# CCM_0023_revB.net
KiCad netlist of a schematic drawn in EAGLE
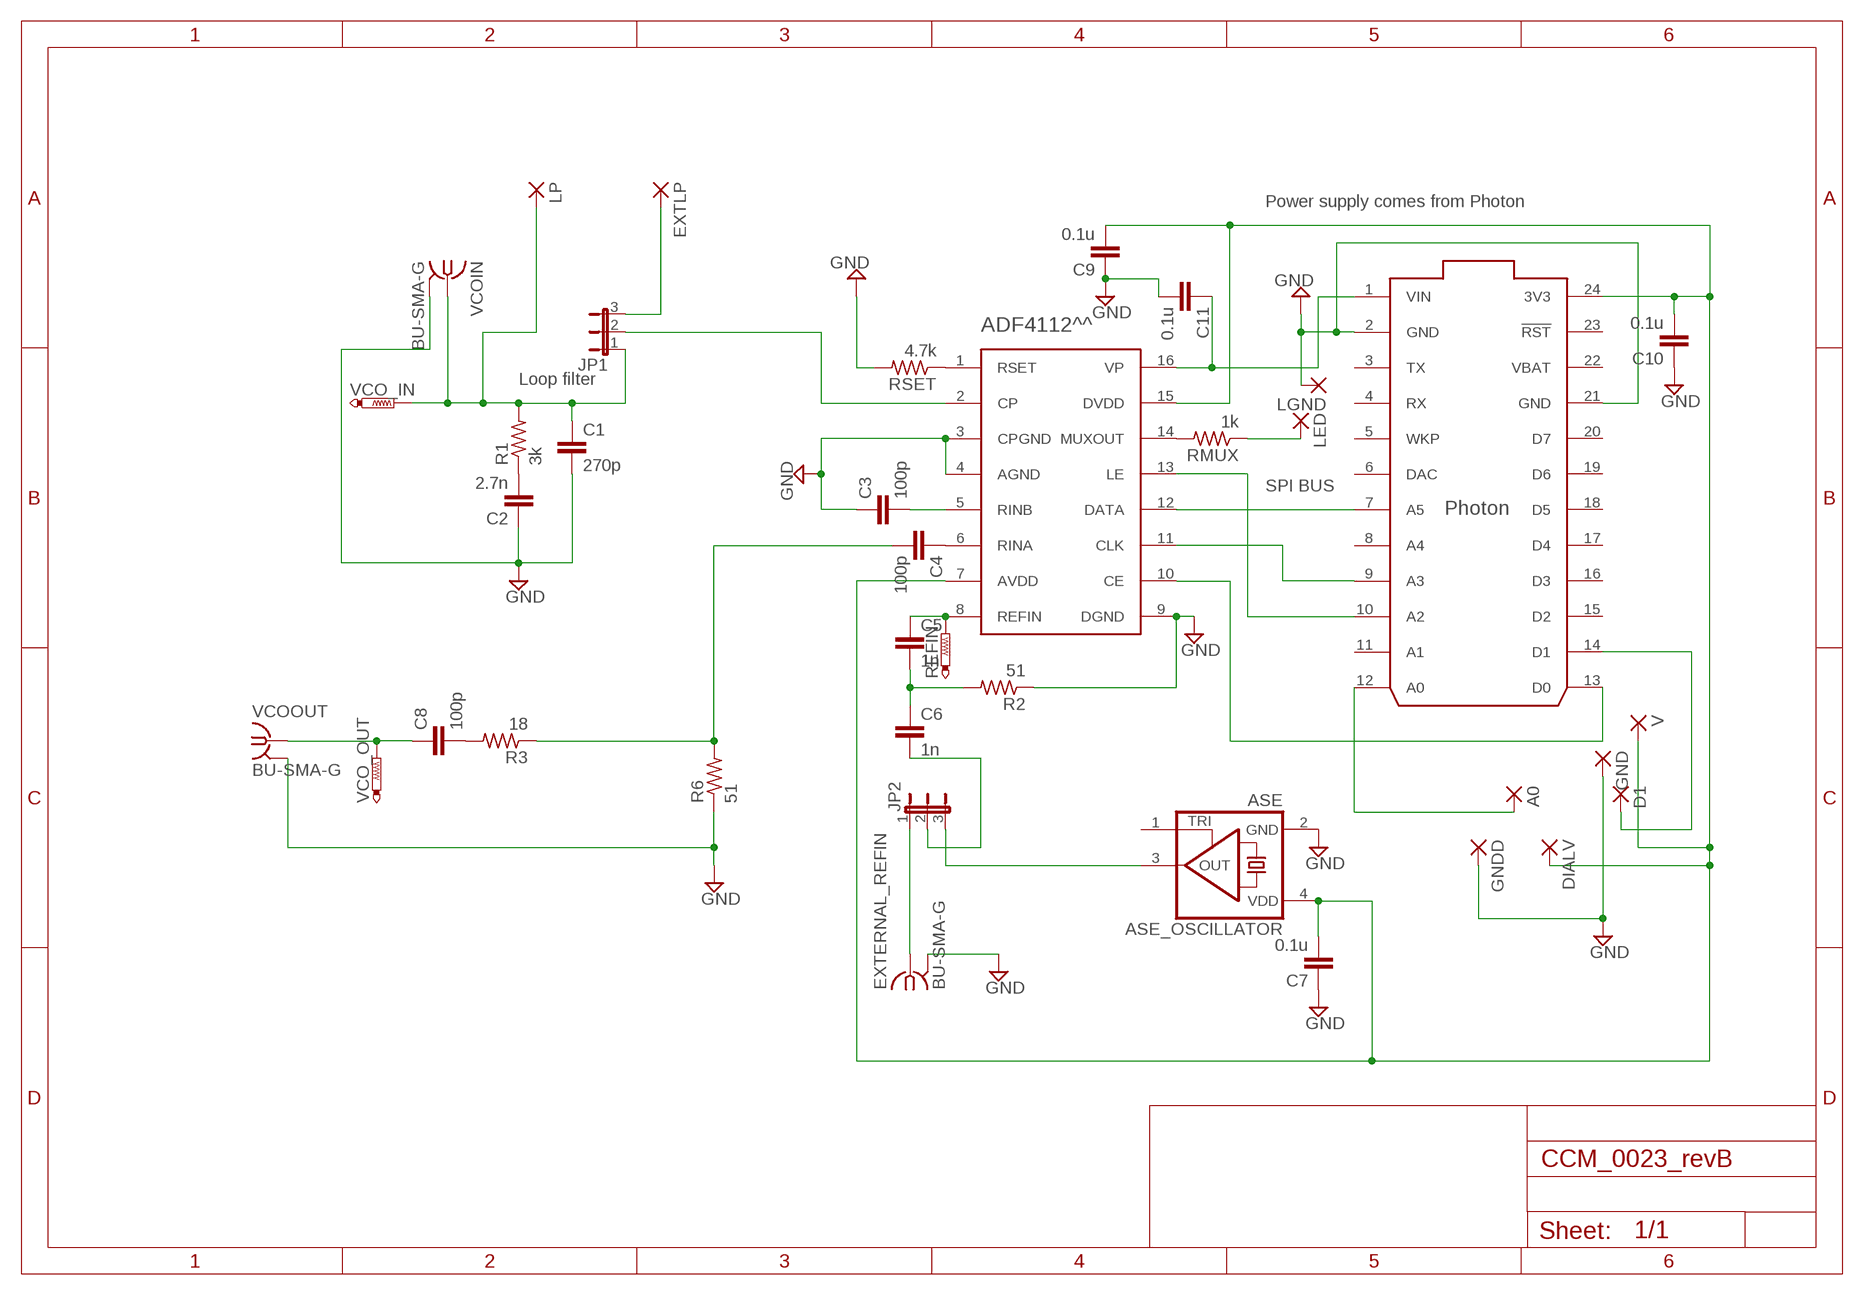
[diagram p0: schematic, sheet 1]

(export (version "E")
  (design (tool "Eeschema 10.0.6"))
  (components
    (comp (ref "A0")
      (value "1,6/0,8")
      (footprint "eagle-import:1,6_0,8")
      (libsource (lib "eagle-import") (part "1,6/0,8"))
    )
    (comp (ref "ADF4112^^")
      (value "ADF4112")
      (footprint "eagle-import:ADF4112")
      (libsource (lib "eagle-import") (part "ADF4112"))
    )
    (comp (ref "ASE_OSCILLATOR")
      (value "ASE")
      (footprint "eagle-import:ASE")
      (libsource (lib "eagle-import") (part "ASE"))
    )
    (comp (ref "C1")
      (value "270p")
      (footprint "eagle-import:C0603")
      (libsource (lib "eagle-import") (part "CC0603"))
    )
    (comp (ref "C2")
      (value "2.7n")
      (footprint "eagle-import:C0603")
      (libsource (lib "eagle-import") (part "CC0603"))
    )
    (comp (ref "C3")
      (value "100p")
      (footprint "eagle-import:C0603")
      (libsource (lib "eagle-import") (part "CC0603"))
    )
    (comp (ref "C4")
      (value "100p")
      (footprint "eagle-import:C0603")
      (libsource (lib "eagle-import") (part "CC0603"))
    )
    (comp (ref "C5")
      (value "1n")
      (footprint "eagle-import:C0603")
      (libsource (lib "eagle-import") (part "CC0603"))
    )
    (comp (ref "C6")
      (value "1n")
      (footprint "eagle-import:C0603")
      (libsource (lib "eagle-import") (part "CC0603"))
    )
    (comp (ref "C7")
      (value "0.1u")
      (footprint "eagle-import:C0603")
      (libsource (lib "eagle-import") (part "CC0603"))
    )
    (comp (ref "C8")
      (value "100p")
      (footprint "eagle-import:C0603")
      (libsource (lib "eagle-import") (part "CC0603"))
    )
    (comp (ref "C9")
      (value "0.1u")
      (footprint "eagle-import:C0603")
      (libsource (lib "eagle-import") (part "CC0603"))
    )
    (comp (ref "C10")
      (value "0.1u")
      (footprint "eagle-import:C0603")
      (libsource (lib "eagle-import") (part "CC0603"))
    )
    (comp (ref "C11")
      (value "0.1u")
      (footprint "eagle-import:C0603")
      (libsource (lib "eagle-import") (part "CC0603"))
    )
    (comp (ref "D1")
      (value "1,6/0,8")
      (footprint "eagle-import:1,6_0,8")
      (libsource (lib "eagle-import") (part "1,6/0,8"))
    )
    (comp (ref "DIALV")
      (value "1,6/0,8")
      (footprint "eagle-import:1,6_0,8")
      (libsource (lib "eagle-import") (part "1,6/0,8"))
    )
    (comp (ref "EXTERNAL_REFIN")
      (value "BU-SMA-G")
      (footprint "eagle-import:BU-SMA-G")
      (libsource (lib "eagle-import") (part "BU-SMA-G"))
    )
    (comp (ref "EXTLP")
      (value "1,6/0,8")
      (footprint "eagle-import:1,6_0,8")
      (libsource (lib "eagle-import") (part "1,6/0,8"))
    )
    (comp (ref "GND")
      (value "1,6/0,8")
      (footprint "eagle-import:1,6_0,8")
      (libsource (lib "eagle-import") (part "1,6/0,8"))
    )
    (comp (ref "GNDD")
      (value "1,6/0,8")
      (footprint "eagle-import:1,6_0,8")
      (libsource (lib "eagle-import") (part "1,6/0,8"))
    )
    (comp (ref "JP1")
      (value "JP2E")
      (footprint "eagle-import:JP2")
      (libsource (lib "eagle-import") (part "JP2E"))
    )
    (comp (ref "JP2")
      (value "JP2E")
      (footprint "eagle-import:JP2")
      (libsource (lib "eagle-import") (part "JP2E"))
    )
    (comp (ref "LED")
      (value "1,6/0,8")
      (footprint "eagle-import:1,6_0,8")
      (libsource (lib "eagle-import") (part "1,6/0,8"))
    )
    (comp (ref "LGND")
      (value "1,6/0,8")
      (footprint "eagle-import:1,6_0,8")
      (libsource (lib "eagle-import") (part "1,6/0,8"))
    )
    (comp (ref "LP")
      (value "1,6/0,8")
      (footprint "eagle-import:1,6_0,8")
      (libsource (lib "eagle-import") (part "1,6/0,8"))
    )
    (comp (ref "PHOTON")
      (value "PHOTON_WITH_HEADERS")
      (footprint "eagle-import:PHOTON")
      (libsource (lib "eagle-import") (part "PHOTON_WITH_HEADERS"))
    )
    (comp (ref "R1")
      (value "3k")
      (footprint "eagle-import:R0603")
      (libsource (lib "eagle-import") (part "R-US_R0603"))
    )
    (comp (ref "R2")
      (value "51")
      (footprint "eagle-import:R0603")
      (libsource (lib "eagle-import") (part "R-US_R0603"))
    )
    (comp (ref "R3")
      (value "18")
      (footprint "eagle-import:R0603")
      (libsource (lib "eagle-import") (part "R-US_R0603"))
    )
    (comp (ref "R6")
      (value "51")
      (footprint "eagle-import:R0603")
      (libsource (lib "eagle-import") (part "R-US_R0603"))
    )
    (comp (ref "REFIN")
      (value "PTR1B2,54")
      (footprint "eagle-import:B2,54")
      (libsource (lib "eagle-import") (part "PTR1B2,54"))
    )
    (comp (ref "RMUX")
      (value "1k")
      (footprint "eagle-import:R0603")
      (libsource (lib "eagle-import") (part "R-US_R0603"))
    )
    (comp (ref "RSET")
      (value "4.7k")
      (footprint "eagle-import:R0603")
      (libsource (lib "eagle-import") (part "R-US_R0603"))
    )
    (comp (ref "V")
      (value "1,6/0,8")
      (footprint "eagle-import:1,6_0,8")
      (libsource (lib "eagle-import") (part "1,6/0,8"))
    )
    (comp (ref "VCOIN")
      (value "BU-SMA-G")
      (footprint "eagle-import:BU-SMA-G")
      (libsource (lib "eagle-import") (part "BU-SMA-G"))
    )
    (comp (ref "VCOOUT")
      (value "BU-SMA-G")
      (footprint "eagle-import:BU-SMA-G")
      (libsource (lib "eagle-import") (part "BU-SMA-G"))
    )
    (comp (ref "VCO_IN")
      (value "PTR1B2,54")
      (footprint "eagle-import:B2,54")
      (libsource (lib "eagle-import") (part "PTR1B2,54"))
    )
    (comp (ref "VCO_OUT")
      (value "PTR1B2,54")
      (footprint "eagle-import:B2,54")
      (libsource (lib "eagle-import") (part "PTR1B2,54"))
    )
  )
  (nets
    (net (code "1") (name "/VBAT") (class "Default")
      (node (ref "PHOTON") (pin "22") (pinfunction "VBAT_22") (pintype "power_in"))
    )
    (net (code "2") (name "GND") (class "Default")
      (node (ref "ADF4112^^") (pin "3") (pinfunction "CPGND_3") (pintype "bidirectional"))
      (node (ref "ADF4112^^") (pin "4") (pinfunction "AGND_4") (pintype "bidirectional"))
      (node (ref "ADF4112^^") (pin "9") (pinfunction "DGND_9") (pintype "bidirectional"))
      (node (ref "ASE_OSCILLATOR") (pin "2") (pinfunction "GND_2") (pintype "power_in"))
      (node (ref "C1") (pin "2") (pinfunction "2_2") (pintype "passive"))
      (node (ref "C10") (pin "1") (pinfunction "1_1") (pintype "passive"))
      (node (ref "C11") (pin "2") (pinfunction "2_2") (pintype "passive"))
      (node (ref "C2") (pin "1") (pinfunction "1_1") (pintype "passive"))
      (node (ref "C3") (pin "1") (pinfunction "1_1") (pintype "passive"))
      (node (ref "C7") (pin "1") (pinfunction "1_1") (pintype "passive"))
      (node (ref "C9") (pin "1") (pinfunction "1_1") (pintype "passive"))
      (node (ref "EXTERNAL_REFIN") (pin "2") (pinfunction "2_2") (pintype "passive"))
      (node (ref "EXTERNAL_REFIN") (pin "3") (pinfunction "2_3") (pintype "passive"))
      (node (ref "EXTERNAL_REFIN") (pin "4") (pinfunction "2_4") (pintype "passive"))
      (node (ref "EXTERNAL_REFIN") (pin "5") (pinfunction "2_5") (pintype "passive"))
      (node (ref "GND") (pin "1") (pinfunction "P_1") (pintype "passive"))
      (node (ref "GNDD") (pin "1") (pinfunction "P_1") (pintype "passive"))
      (node (ref "LGND") (pin "1") (pinfunction "P_1") (pintype "passive"))
      (node (ref "PHOTON") (pin "2") (pinfunction "GND_2") (pintype "power_in"))
      (node (ref "PHOTON") (pin "21") (pinfunction "GND_21") (pintype "power_in"))
      (node (ref "R2") (pin "1") (pinfunction "1_1") (pintype "passive"))
      (node (ref "R6") (pin "1") (pinfunction "1_1") (pintype "passive"))
      (node (ref "RSET") (pin "2") (pinfunction "2_2") (pintype "passive"))
      (node (ref "VCOIN") (pin "2") (pinfunction "2_2") (pintype "passive"))
      (node (ref "VCOIN") (pin "3") (pinfunction "2_3") (pintype "passive"))
      (node (ref "VCOIN") (pin "4") (pinfunction "2_4") (pintype "passive"))
      (node (ref "VCOIN") (pin "5") (pinfunction "2_5") (pintype "passive"))
      (node (ref "VCOOUT") (pin "2") (pinfunction "2_2") (pintype "passive"))
      (node (ref "VCOOUT") (pin "3") (pinfunction "2_3") (pintype "passive"))
      (node (ref "VCOOUT") (pin "4") (pinfunction "2_4") (pintype "passive"))
      (node (ref "VCOOUT") (pin "5") (pinfunction "2_5") (pintype "passive"))
    )
    (net (code "3") (name "Net-(A0-P)") (class "Default")
      (node (ref "A0") (pin "1") (pinfunction "P_1") (pintype "passive"))
      (node (ref "PHOTON") (pin "12") (pinfunction "A0_12") (pintype "bidirectional"))
    )
    (net (code "4") (name "Net-(ADF4112^^-AVDD)") (class "Default")
      (node (ref "ADF4112^^") (pin "15") (pinfunction "DVDD_15") (pintype "power_in"))
      (node (ref "ADF4112^^") (pin "7") (pinfunction "AVDD_7") (pintype "power_in"))
      (node (ref "ASE_OSCILLATOR") (pin "4") (pinfunction "VDD_4") (pintype "power_in"))
      (node (ref "C10") (pin "2") (pinfunction "2_2") (pintype "passive"))
      (node (ref "C7") (pin "2") (pinfunction "2_2") (pintype "passive"))
      (node (ref "C9") (pin "2") (pinfunction "2_2") (pintype "passive"))
      (node (ref "DIALV") (pin "1") (pinfunction "P_1") (pintype "passive"))
      (node (ref "PHOTON") (pin "24") (pinfunction "3V3_24") (pintype "power_in"))
      (node (ref "V") (pin "1") (pinfunction "P_1") (pintype "passive"))
    )
    (net (code "5") (name "Net-(ADF4112^^-CE)") (class "Default")
      (node (ref "ADF4112^^") (pin "10") (pinfunction "CE_10") (pintype "bidirectional"))
      (node (ref "PHOTON") (pin "13") (pinfunction "D0_13") (pintype "bidirectional"))
    )
    (net (code "6") (name "Net-(ADF4112^^-CLK)") (class "Default")
      (node (ref "ADF4112^^") (pin "11") (pinfunction "CLK_11") (pintype "bidirectional"))
      (node (ref "PHOTON") (pin "9") (pinfunction "A3_9") (pintype "bidirectional"))
    )
    (net (code "7") (name "Net-(ADF4112^^-CP)") (class "Default")
      (node (ref "ADF4112^^") (pin "2") (pinfunction "CP_2") (pintype "bidirectional"))
      (node (ref "JP1") (pin "2") (pinfunction "2_2") (pintype "passive"))
    )
    (net (code "8") (name "Net-(ADF4112^^-DATA)") (class "Default")
      (node (ref "ADF4112^^") (pin "12") (pinfunction "DATA_12") (pintype "bidirectional"))
      (node (ref "PHOTON") (pin "7") (pinfunction "A5_7") (pintype "bidirectional"))
    )
    (net (code "9") (name "Net-(ADF4112^^-LE)") (class "Default")
      (node (ref "ADF4112^^") (pin "13") (pinfunction "LE_13") (pintype "bidirectional"))
      (node (ref "PHOTON") (pin "10") (pinfunction "A2_10") (pintype "bidirectional"))
    )
    (net (code "10") (name "Net-(ADF4112^^-MUXOUT)") (class "Default")
      (node (ref "ADF4112^^") (pin "14") (pinfunction "MUXOUT_14") (pintype "bidirectional"))
      (node (ref "RMUX") (pin "2") (pinfunction "2_2") (pintype "passive"))
    )
    (net (code "11") (name "Net-(ADF4112^^-REFIN)") (class "Default")
      (node (ref "ADF4112^^") (pin "8") (pinfunction "REFIN_8") (pintype "bidirectional"))
      (node (ref "C5") (pin "1") (pinfunction "1_1") (pintype "passive"))
      (node (ref "REFIN") (pin "TP") (pinfunction "TP_TP") (pintype "input"))
    )
    (net (code "12") (name "Net-(ADF4112^^-RINA)") (class "Default")
      (node (ref "ADF4112^^") (pin "6") (pinfunction "RINA_6") (pintype "bidirectional"))
      (node (ref "C4") (pin "1") (pinfunction "1_1") (pintype "passive"))
    )
    (net (code "13") (name "Net-(ADF4112^^-RINB)") (class "Default")
      (node (ref "ADF4112^^") (pin "5") (pinfunction "RINB_5") (pintype "bidirectional"))
      (node (ref "C3") (pin "2") (pinfunction "2_2") (pintype "passive"))
    )
    (net (code "14") (name "Net-(ADF4112^^-RSET)") (class "Default")
      (node (ref "ADF4112^^") (pin "1") (pinfunction "RSET_1") (pintype "bidirectional"))
      (node (ref "RSET") (pin "1") (pinfunction "1_1") (pintype "passive"))
    )
    (net (code "15") (name "Net-(ADF4112^^-VP)") (class "Default")
      (node (ref "ADF4112^^") (pin "16") (pinfunction "VP_16") (pintype "power_in"))
      (node (ref "C11") (pin "1") (pinfunction "1_1") (pintype "passive"))
      (node (ref "PHOTON") (pin "1") (pinfunction "VIN_1") (pintype "power_in"))
    )
    (net (code "16") (name "Net-(ASE_OSCILLATOR-OUT)") (class "Default")
      (node (ref "ASE_OSCILLATOR") (pin "3") (pinfunction "OUT_3") (pintype "output"))
      (node (ref "JP2") (pin "3") (pinfunction "3_3") (pintype "passive"))
    )
    (net (code "17") (name "Net-(C2-Pad2)") (class "Default")
      (node (ref "C2") (pin "2") (pinfunction "2_2") (pintype "passive"))
      (node (ref "R1") (pin "1") (pinfunction "1_1") (pintype "passive"))
    )
    (net (code "18") (name "Net-(C4-Pad2)") (class "Default")
      (node (ref "C4") (pin "2") (pinfunction "2_2") (pintype "passive"))
      (node (ref "R3") (pin "1") (pinfunction "1_1") (pintype "passive"))
      (node (ref "R6") (pin "2") (pinfunction "2_2") (pintype "passive"))
    )
    (net (code "19") (name "Net-(C5-Pad2)") (class "Default")
      (node (ref "C5") (pin "2") (pinfunction "2_2") (pintype "passive"))
      (node (ref "C6") (pin "1") (pinfunction "1_1") (pintype "passive"))
      (node (ref "R2") (pin "2") (pinfunction "2_2") (pintype "passive"))
    )
    (net (code "20") (name "Net-(C6-Pad2)") (class "Default")
      (node (ref "C6") (pin "2") (pinfunction "2_2") (pintype "passive"))
      (node (ref "JP2") (pin "2") (pinfunction "2_2") (pintype "passive"))
    )
    (net (code "21") (name "Net-(C8-Pad1)") (class "Default")
      (node (ref "C8") (pin "1") (pinfunction "1_1") (pintype "passive"))
      (node (ref "VCOOUT") (pin "1") (pinfunction "1_1") (pintype "passive"))
      (node (ref "VCO_OUT") (pin "TP") (pinfunction "TP_TP") (pintype "input"))
    )
    (net (code "22") (name "Net-(C8-Pad2)") (class "Default")
      (node (ref "C8") (pin "2") (pinfunction "2_2") (pintype "passive"))
      (node (ref "R3") (pin "2") (pinfunction "2_2") (pintype "passive"))
    )
    (net (code "23") (name "Net-(D1-P)") (class "Default")
      (node (ref "D1") (pin "1") (pinfunction "P_1") (pintype "passive"))
      (node (ref "PHOTON") (pin "14") (pinfunction "D1_14") (pintype "bidirectional"))
    )
    (net (code "24") (name "Net-(EXTERNAL_REFIN-Pad1)") (class "Default")
      (node (ref "EXTERNAL_REFIN") (pin "1") (pinfunction "1_1") (pintype "passive"))
      (node (ref "JP2") (pin "1") (pinfunction "1_1") (pintype "passive"))
    )
    (net (code "25") (name "Net-(EXTLP-P)") (class "Default")
      (node (ref "EXTLP") (pin "1") (pinfunction "P_1") (pintype "passive"))
      (node (ref "JP1") (pin "3") (pinfunction "3_3") (pintype "passive"))
    )
    (net (code "26") (name "Net-(LED-P)") (class "Default")
      (node (ref "LED") (pin "1") (pinfunction "P_1") (pintype "passive"))
      (node (ref "RMUX") (pin "1") (pinfunction "1_1") (pintype "passive"))
    )
    (net (code "27") (name "Net-(LP-P)") (class "Default")
      (node (ref "C1") (pin "1") (pinfunction "1_1") (pintype "passive"))
      (node (ref "JP1") (pin "1") (pinfunction "1_1") (pintype "passive"))
      (node (ref "LP") (pin "1") (pinfunction "P_1") (pintype "passive"))
      (node (ref "R1") (pin "2") (pinfunction "2_2") (pintype "passive"))
      (node (ref "VCOIN") (pin "1") (pinfunction "1_1") (pintype "passive"))
      (node (ref "VCO_IN") (pin "TP") (pinfunction "TP_TP") (pintype "input"))
    )
    (net (code "28") (name "unconnected-(ASE_OSCILLATOR-TRI-Pad1)") (class "Default")
      (node (ref "ASE_OSCILLATOR") (pin "1") (pinfunction "TRI_1") (pintype "input"))
    )
    (net (code "29") (name "unconnected-(PHOTON-A1-Pad11)") (class "Default")
      (node (ref "PHOTON") (pin "11") (pinfunction "A1_11") (pintype "bidirectional"))
    )
    (net (code "30") (name "unconnected-(PHOTON-A4-Pad8)") (class "Default")
      (node (ref "PHOTON") (pin "8") (pinfunction "A4_8") (pintype "bidirectional"))
    )
    (net (code "31") (name "unconnected-(PHOTON-D2-Pad15)") (class "Default")
      (node (ref "PHOTON") (pin "15") (pinfunction "D2_15") (pintype "bidirectional"))
    )
    (net (code "32") (name "unconnected-(PHOTON-D3-Pad16)") (class "Default")
      (node (ref "PHOTON") (pin "16") (pinfunction "D3_16") (pintype "bidirectional"))
    )
    (net (code "33") (name "unconnected-(PHOTON-D4-Pad17)") (class "Default")
      (node (ref "PHOTON") (pin "17") (pinfunction "D4_17") (pintype "bidirectional"))
    )
    (net (code "34") (name "unconnected-(PHOTON-D5-Pad18)") (class "Default")
      (node (ref "PHOTON") (pin "18") (pinfunction "D5_18") (pintype "bidirectional"))
    )
    (net (code "35") (name "unconnected-(PHOTON-D6-Pad19)") (class "Default")
      (node (ref "PHOTON") (pin "19") (pinfunction "D6_19") (pintype "bidirectional"))
    )
    (net (code "36") (name "unconnected-(PHOTON-D7-Pad20)") (class "Default")
      (node (ref "PHOTON") (pin "20") (pinfunction "D7_20") (pintype "bidirectional"))
    )
    (net (code "37") (name "unconnected-(PHOTON-DAC-Pad6)") (class "Default")
      (node (ref "PHOTON") (pin "6") (pinfunction "DAC_6") (pintype "bidirectional"))
    )
    (net (code "38") (name "unconnected-(PHOTON-RX-Pad4)") (class "Default")
      (node (ref "PHOTON") (pin "4") (pinfunction "RX_4") (pintype "bidirectional"))
    )
    (net (code "39") (name "unconnected-(PHOTON-TX-Pad3)") (class "Default")
      (node (ref "PHOTON") (pin "3") (pinfunction "TX_3") (pintype "bidirectional"))
    )
    (net (code "40") (name "unconnected-(PHOTON-WKP-Pad5)") (class "Default")
      (node (ref "PHOTON") (pin "5") (pinfunction "WKP_5") (pintype "bidirectional"))
    )
    (net (code "41") (name "unconnected-(PHOTON-~{RST}-Pad23)") (class "Default")
      (node (ref "PHOTON") (pin "23") (pinfunction "~{RST}_23") (pintype "bidirectional"))
    )
  )
)
